# MCU.net
KiCad netlist of a schematic drawn in Altium Designer
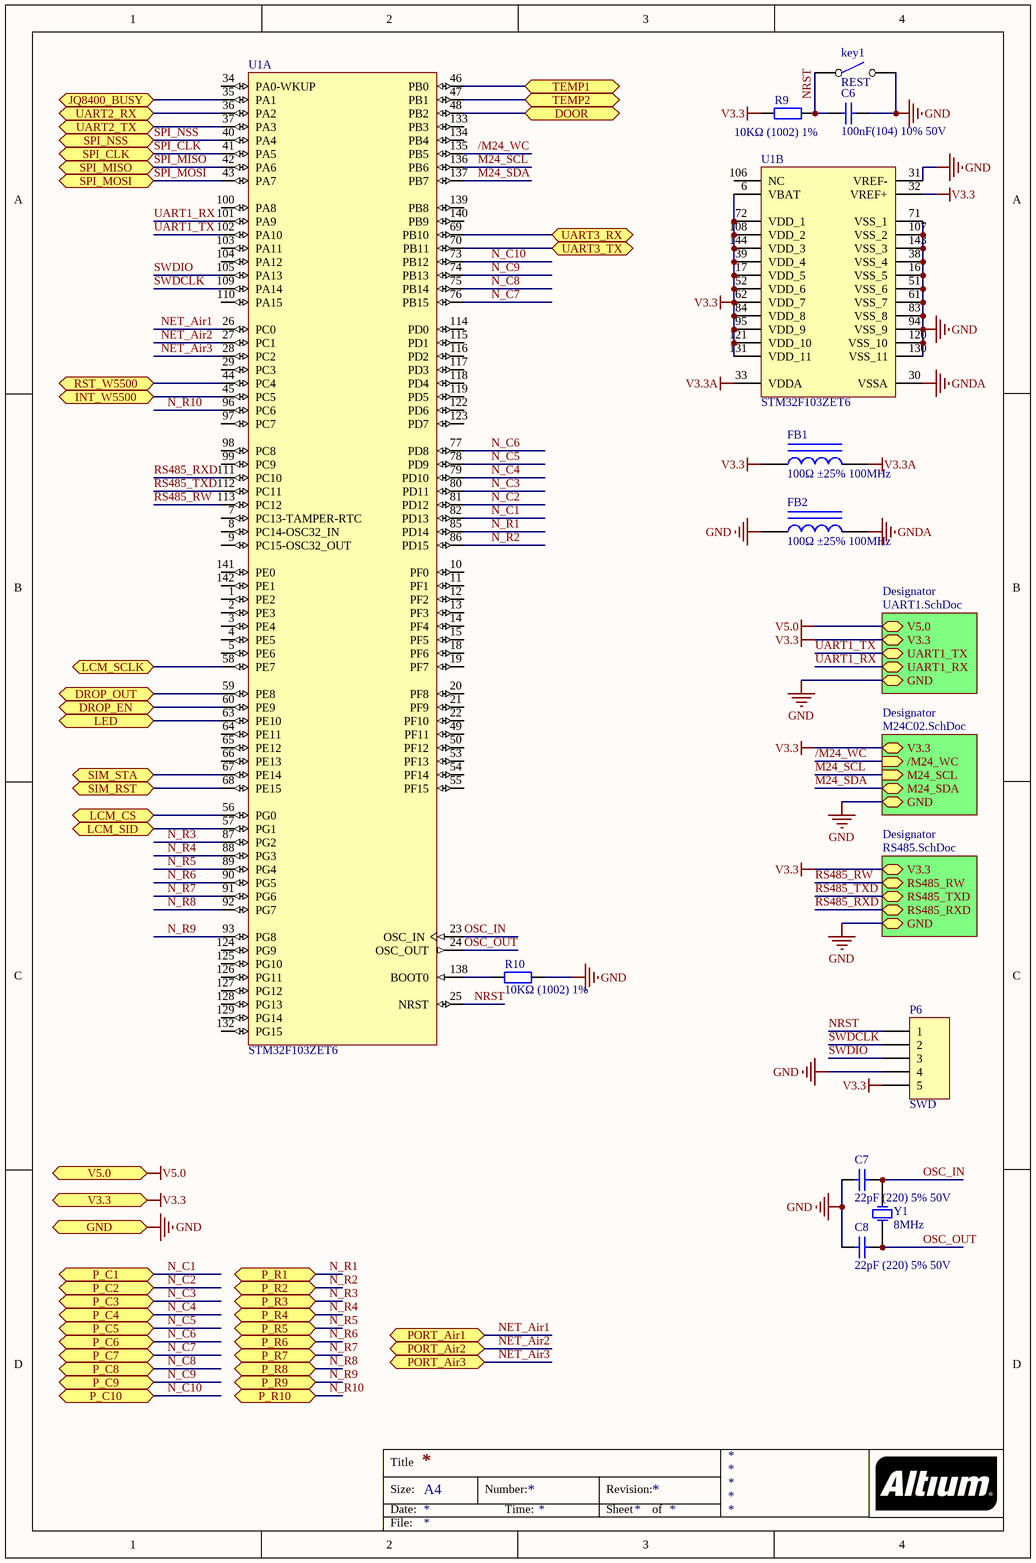
[diagram p0: MCU.SchDoc]

(export (version "E")
  (design (tool "Eeschema 10.0.6"))
  (components
    (comp (ref "C6")
      (value "100nF(104) 10% 50V")
      (footprint "0805_C")
      (description "贴片电容")
      (libsource (lib "Miscellaneous Devices LC") (part "0805 100nF(104) 10% 50V"))
    )
    (comp (ref "C7")
      (value "22pF (220) 5% 50V")
      (footprint "0805_C")
      (description "贴片电容")
      (libsource (lib "Miscellaneous Devices LC") (part "0805 22pF (220) 5% 50V"))
    )
    (comp (ref "C8")
      (value "22pF (220) 5% 50V")
      (footprint "0805_C")
      (description "贴片电容")
      (libsource (lib "Miscellaneous Devices LC") (part "0805 22pF (220) 5% 50V"))
    )
    (comp (ref "FB1")
      (value "100Ω ±25% 100MHz")
      (footprint "0805_L")
      (description "贴片磁珠")
      (libsource (lib "Miscellaneous Devices LC") (part "0805 100Ω 25% 100MHz"))
    )
    (comp (ref "FB2")
      (value "100Ω ±25% 100MHz")
      (footprint "0805_L")
      (description "贴片磁珠")
      (libsource (lib "Miscellaneous Devices LC") (part "0805 100Ω 25% 100MHz"))
    )
    (comp (ref "key1") (value "REST") (footprint "key") (libsource (lib "开关") (part "单刀开关")))
    (comp (ref "P6")
      (value "SWD")
      (footprint "HDR1X5")
      (description "Header, 5-Pin")
      (fields (field (name "PUBLISHER") "Altium Limited"))
      (libsource (lib "Miscellaneous Connectors") (part "Header 5"))
    )
    (comp (ref "R9")
      (value "10KΩ (1002) 1%")
      (footprint "0805_R")
      (description "贴片电阻")
      (libsource (lib "") (part "0805 10KΩ (1002) 1%_1"))
    )
    (comp (ref "R10")
      (value "10KΩ (1002) 1%")
      (footprint "0805_R")
      (description "贴片电阻")
      (libsource (lib "Miscellaneous Devices LC") (part "0805 10KΩ (1002) 1%"))
    )
    (comp (ref "U1")
      (value "STM32F103ZET6")
      (footprint "LQFP-144_20x20x05P")
      (description "ARM")
      (libsource (lib "Miscellaneous Devices LC") (part "STM32F103ZET6"))
    )
    (comp (ref "Y1")
      (value "8MHz")
      (footprint "SMD-5032_2P")
      (description "贴片晶振")
      (libsource (lib "Miscellaneous Devices LC") (part "SMD-5032_2P 8MHz 20ppm 20pF"))
    )
  )
  (nets
    (net (code "1") (name "/DOOR") (class "Default")
      (node (ref "U1") (pin "48") (pinfunction "PB2_48") (pintype "bidirectional"))
    )
    (net (code "2") (name "/DROP_EN") (class "Default")
      (node (ref "U1") (pin "60") (pinfunction "PE9_60") (pintype "bidirectional"))
    )
    (net (code "3") (name "/DROP_OUT") (class "Default")
      (node (ref "U1") (pin "59") (pinfunction "PE8_59") (pintype "bidirectional"))
    )
    (net (code "4") (name "/INT_W5500") (class "Default")
      (node (ref "U1") (pin "45") (pinfunction "PC5_45") (pintype "bidirectional"))
    )
    (net (code "5") (name "/JQ8400_BUSY") (class "Default")
      (node (ref "U1") (pin "35") (pinfunction "PA1_35") (pintype "bidirectional"))
    )
    (net (code "6") (name "/LCM_CS") (class "Default")
      (node (ref "U1") (pin "56") (pinfunction "PG0_56") (pintype "bidirectional"))
    )
    (net (code "7") (name "/LCM_SCLK") (class "Default")
      (node (ref "U1") (pin "58") (pinfunction "PE7_58") (pintype "bidirectional"))
    )
    (net (code "8") (name "/LCM_SID") (class "Default")
      (node (ref "U1") (pin "57") (pinfunction "PG1_57") (pintype "bidirectional"))
    )
    (net (code "9") (name "/LED") (class "Default")
      (node (ref "U1") (pin "63") (pinfunction "PE10_63") (pintype "bidirectional"))
    )
    (net (code "10") (name "/M24_SCL") (class "Default")
      (node (ref "U1") (pin "136") (pinfunction "PB6_136") (pintype "bidirectional"))
    )
    (net (code "11") (name "/M24_SDA") (class "Default")
      (node (ref "U1") (pin "137") (pinfunction "PB7_137") (pintype "bidirectional"))
    )
    (net (code "12") (name "/NET_Air1") (class "Default")
      (node (ref "U1") (pin "26") (pinfunction "PC0_26") (pintype "bidirectional"))
    )
    (net (code "13") (name "/NET_Air2") (class "Default")
      (node (ref "U1") (pin "27") (pinfunction "PC1_27") (pintype "bidirectional"))
    )
    (net (code "14") (name "/NET_Air3") (class "Default")
      (node (ref "U1") (pin "28") (pinfunction "PC2_28") (pintype "bidirectional"))
    )
    (net (code "15") (name "/NRST") (class "Default")
      (node (ref "C6") (pin "1") (pinfunction "1_1") (pintype "passive"))
      (node (ref "P6") (pin "1") (pinfunction "1_1") (pintype "passive"))
      (node (ref "R9") (pin "1") (pinfunction "1_1") (pintype "passive"))
      (node (ref "U1") (pin "25") (pinfunction "NRST_25") (pintype "bidirectional"))
      (node (ref "key1") (pin "1") (pinfunction "1_1") (pintype "passive"))
    )
    (net (code "16") (name "/N_C1") (class "Default")
      (node (ref "U1") (pin "82") (pinfunction "PD13_82") (pintype "bidirectional"))
    )
    (net (code "17") (name "/N_C2") (class "Default")
      (node (ref "U1") (pin "81") (pinfunction "PD12_81") (pintype "bidirectional"))
    )
    (net (code "18") (name "/N_C3") (class "Default")
      (node (ref "U1") (pin "80") (pinfunction "PD11_80") (pintype "bidirectional"))
    )
    (net (code "19") (name "/N_C4") (class "Default")
      (node (ref "U1") (pin "79") (pinfunction "PD10_79") (pintype "bidirectional"))
    )
    (net (code "20") (name "/N_C5") (class "Default")
      (node (ref "U1") (pin "78") (pinfunction "PD9_78") (pintype "bidirectional"))
    )
    (net (code "21") (name "/N_C6") (class "Default")
      (node (ref "U1") (pin "77") (pinfunction "PD8_77") (pintype "bidirectional"))
    )
    (net (code "22") (name "/N_C7") (class "Default")
      (node (ref "U1") (pin "76") (pinfunction "PB15_76") (pintype "bidirectional"))
    )
    (net (code "23") (name "/N_C8") (class "Default")
      (node (ref "U1") (pin "75") (pinfunction "PB14_75") (pintype "bidirectional"))
    )
    (net (code "24") (name "/N_C9") (class "Default")
      (node (ref "U1") (pin "74") (pinfunction "PB13_74") (pintype "bidirectional"))
    )
    (net (code "25") (name "/N_C10") (class "Default")
      (node (ref "U1") (pin "73") (pinfunction "PB12_73") (pintype "bidirectional"))
    )
    (net (code "26") (name "/N_R1") (class "Default")
      (node (ref "U1") (pin "85") (pinfunction "PD14_85") (pintype "bidirectional"))
    )
    (net (code "27") (name "/N_R2") (class "Default")
      (node (ref "U1") (pin "86") (pinfunction "PD15_86") (pintype "bidirectional"))
    )
    (net (code "28") (name "/N_R3") (class "Default")
      (node (ref "U1") (pin "87") (pinfunction "PG2_87") (pintype "bidirectional"))
    )
    (net (code "29") (name "/N_R4") (class "Default")
      (node (ref "U1") (pin "88") (pinfunction "PG3_88") (pintype "bidirectional"))
    )
    (net (code "30") (name "/N_R5") (class "Default")
      (node (ref "U1") (pin "89") (pinfunction "PG4_89") (pintype "bidirectional"))
    )
    (net (code "31") (name "/N_R6") (class "Default")
      (node (ref "U1") (pin "90") (pinfunction "PG5_90") (pintype "bidirectional"))
    )
    (net (code "32") (name "/N_R7") (class "Default")
      (node (ref "U1") (pin "91") (pinfunction "PG6_91") (pintype "bidirectional"))
    )
    (net (code "33") (name "/N_R8") (class "Default")
      (node (ref "U1") (pin "92") (pinfunction "PG7_92") (pintype "bidirectional"))
    )
    (net (code "34") (name "/N_R9") (class "Default")
      (node (ref "U1") (pin "93") (pinfunction "PG8_93") (pintype "bidirectional"))
    )
    (net (code "35") (name "/N_R10") (class "Default")
      (node (ref "U1") (pin "96") (pinfunction "PC6_96") (pintype "bidirectional"))
    )
    (net (code "36") (name "/OSC_IN") (class "Default")
      (node (ref "C7") (pin "1") (pinfunction "1_1") (pintype "passive"))
      (node (ref "U1") (pin "23") (pinfunction "OSC_IN_23") (pintype "input"))
      (node (ref "Y1") (pin "1") (pinfunction "OSC1_1") (pintype "passive"))
    )
    (net (code "37") (name "/OSC_OUT") (class "Default")
      (node (ref "C8") (pin "1") (pinfunction "1_1") (pintype "passive"))
      (node (ref "U1") (pin "24") (pinfunction "OSC_OUT_24") (pintype "output"))
      (node (ref "Y1") (pin "2") (pinfunction "OSC2_2") (pintype "passive"))
    )
    (net (code "38") (name "/RS485_RW") (class "Default")
      (node (ref "U1") (pin "113") (pinfunction "PC12_113") (pintype "bidirectional"))
    )
    (net (code "39") (name "/RS485_RXD") (class "Default")
      (node (ref "U1") (pin "111") (pinfunction "PC10_111") (pintype "bidirectional"))
    )
    (net (code "40") (name "/RS485_TXD") (class "Default")
      (node (ref "U1") (pin "112") (pinfunction "PC11_112") (pintype "bidirectional"))
    )
    (net (code "41") (name "/RST_W5500") (class "Default")
      (node (ref "U1") (pin "44") (pinfunction "PC4_44") (pintype "bidirectional"))
    )
    (net (code "42") (name "/SIM_RST") (class "Default")
      (node (ref "U1") (pin "68") (pinfunction "PE15_68") (pintype "bidirectional"))
    )
    (net (code "43") (name "/SIM_STA") (class "Default")
      (node (ref "U1") (pin "67") (pinfunction "PE14_67") (pintype "bidirectional"))
    )
    (net (code "44") (name "/SPI_CLK") (class "Default")
      (node (ref "U1") (pin "41") (pinfunction "PA5_41") (pintype "bidirectional"))
    )
    (net (code "45") (name "/SPI_MISO") (class "Default")
      (node (ref "U1") (pin "42") (pinfunction "PA6_42") (pintype "bidirectional"))
    )
    (net (code "46") (name "/SPI_MOSI") (class "Default")
      (node (ref "U1") (pin "43") (pinfunction "PA7_43") (pintype "bidirectional"))
    )
    (net (code "47") (name "/SPI_NSS") (class "Default")
      (node (ref "U1") (pin "40") (pinfunction "PA4_40") (pintype "bidirectional"))
    )
    (net (code "48") (name "/SWDCLK") (class "Default")
      (node (ref "P6") (pin "2") (pinfunction "2_2") (pintype "passive"))
      (node (ref "U1") (pin "109") (pinfunction "PA14_109") (pintype "bidirectional"))
    )
    (net (code "49") (name "/SWDIO") (class "Default")
      (node (ref "P6") (pin "3") (pinfunction "3_3") (pintype "passive"))
      (node (ref "U1") (pin "105") (pinfunction "PA13_105") (pintype "bidirectional"))
    )
    (net (code "50") (name "/TEMP1") (class "Default")
      (node (ref "U1") (pin "46") (pinfunction "PB0_46") (pintype "bidirectional"))
    )
    (net (code "51") (name "/TEMP2") (class "Default")
      (node (ref "U1") (pin "47") (pinfunction "PB1_47") (pintype "bidirectional"))
    )
    (net (code "52") (name "/UART1_RX") (class "Default")
      (node (ref "U1") (pin "101") (pinfunction "PA9_101") (pintype "bidirectional"))
    )
    (net (code "53") (name "/UART1_TX") (class "Default")
      (node (ref "U1") (pin "102") (pinfunction "PA10_102") (pintype "bidirectional"))
    )
    (net (code "54") (name "/UART2_RX") (class "Default")
      (node (ref "U1") (pin "36") (pinfunction "PA2_36") (pintype "bidirectional"))
    )
    (net (code "55") (name "/UART2_TX") (class "Default")
      (node (ref "U1") (pin "37") (pinfunction "PA3_37") (pintype "bidirectional"))
    )
    (net (code "56") (name "/UART3_RX") (class "Default")
      (node (ref "U1") (pin "69") (pinfunction "PB10_69") (pintype "bidirectional"))
    )
    (net (code "57") (name "/UART3_TX") (class "Default")
      (node (ref "U1") (pin "70") (pinfunction "PB11_70") (pintype "bidirectional"))
    )
    (net (code "58") (name "/{slash}M24_WC") (class "Default")
      (node (ref "U1") (pin "135") (pinfunction "PB5_135") (pintype "bidirectional"))
    )
    (net (code "59") (name "GND") (class "Default")
      (node (ref "C6") (pin "2") (pinfunction "2_2") (pintype "passive"))
      (node (ref "C7") (pin "2") (pinfunction "2_2") (pintype "passive"))
      (node (ref "C8") (pin "2") (pinfunction "2_2") (pintype "passive"))
      (node (ref "FB2") (pin "1") (pinfunction "1_1") (pintype "passive"))
      (node (ref "P6") (pin "4") (pinfunction "4_4") (pintype "passive"))
      (node (ref "R10") (pin "2") (pinfunction "2_2") (pintype "passive"))
      (node (ref "U1") (pin "107") (pinfunction "VSS_2_107") (pintype "power_in"))
      (node (ref "U1") (pin "120") (pinfunction "VSS_10_120") (pintype "power_in"))
      (node (ref "U1") (pin "130") (pinfunction "VSS_11_130") (pintype "power_in"))
      (node (ref "U1") (pin "143") (pinfunction "VSS_3_143") (pintype "power_in"))
      (node (ref "U1") (pin "16") (pinfunction "VSS_5_16") (pintype "power_in"))
      (node (ref "U1") (pin "31") (pinfunction "VREF-_31") (pintype "power_in"))
      (node (ref "U1") (pin "38") (pinfunction "VSS_4_38") (pintype "power_in"))
      (node (ref "U1") (pin "51") (pinfunction "VSS_6_51") (pintype "power_in"))
      (node (ref "U1") (pin "61") (pinfunction "VSS_7_61") (pintype "power_in"))
      (node (ref "U1") (pin "71") (pinfunction "VSS_1_71") (pintype "power_in"))
      (node (ref "U1") (pin "83") (pinfunction "VSS_8_83") (pintype "power_in"))
      (node (ref "U1") (pin "94") (pinfunction "VSS_9_94") (pintype "power_in"))
      (node (ref "key1") (pin "2") (pinfunction "2_2") (pintype "passive"))
    )
    (net (code "60") (name "GNDA") (class "Default")
      (node (ref "FB2") (pin "2") (pinfunction "2_2") (pintype "passive"))
      (node (ref "U1") (pin "30") (pinfunction "VSSA_30") (pintype "power_in"))
    )
    (net (code "61") (name "Net-(U1A-BOOT0)") (class "Default")
      (node (ref "R10") (pin "1") (pinfunction "1_1") (pintype "passive"))
      (node (ref "U1") (pin "138") (pinfunction "BOOT0_138") (pintype "input"))
    )
    (net (code "62") (name "V3.3") (class "Default")
      (node (ref "FB1") (pin "1") (pinfunction "1_1") (pintype "passive"))
      (node (ref "P6") (pin "5") (pinfunction "5_5") (pintype "passive"))
      (node (ref "R9") (pin "2") (pinfunction "2_2") (pintype "passive"))
      (node (ref "U1") (pin "108") (pinfunction "VDD_2_108") (pintype "power_in"))
      (node (ref "U1") (pin "121") (pinfunction "VDD_10_121") (pintype "power_in"))
      (node (ref "U1") (pin "131") (pinfunction "VDD_11_131") (pintype "power_in"))
      (node (ref "U1") (pin "144") (pinfunction "VDD_3_144") (pintype "power_in"))
      (node (ref "U1") (pin "17") (pinfunction "VDD_5_17") (pintype "power_in"))
      (node (ref "U1") (pin "32") (pinfunction "VREF+_32") (pintype "power_in"))
      (node (ref "U1") (pin "39") (pinfunction "VDD_4_39") (pintype "power_in"))
      (node (ref "U1") (pin "52") (pinfunction "VDD_6_52") (pintype "power_in"))
      (node (ref "U1") (pin "6") (pinfunction "VBAT_6") (pintype "power_in"))
      (node (ref "U1") (pin "62") (pinfunction "VDD_7_62") (pintype "power_in"))
      (node (ref "U1") (pin "72") (pinfunction "VDD_1_72") (pintype "power_in"))
      (node (ref "U1") (pin "84") (pinfunction "VDD_8_84") (pintype "power_in"))
      (node (ref "U1") (pin "95") (pinfunction "VDD_9_95") (pintype "power_in"))
    )
    (net (code "63") (name "V3.3A") (class "Default")
      (node (ref "FB1") (pin "2") (pinfunction "2_2") (pintype "passive"))
      (node (ref "U1") (pin "33") (pinfunction "VDDA_33") (pintype "power_in"))
    )
    (net (code "65") (name "unconnected-(U1A-PA0-WKUP-Pad34)") (class "Default")
      (node (ref "U1") (pin "34") (pinfunction "PA0-WKUP_34") (pintype "bidirectional"))
    )
    (net (code "66") (name "unconnected-(U1A-PA8-Pad100)") (class "Default")
      (node (ref "U1") (pin "100") (pinfunction "PA8_100") (pintype "bidirectional"))
    )
    (net (code "67") (name "unconnected-(U1A-PA11-Pad103)") (class "Default")
      (node (ref "U1") (pin "103") (pinfunction "PA11_103") (pintype "bidirectional"))
    )
    (net (code "68") (name "unconnected-(U1A-PA12-Pad104)") (class "Default")
      (node (ref "U1") (pin "104") (pinfunction "PA12_104") (pintype "bidirectional"))
    )
    (net (code "69") (name "unconnected-(U1A-PA15-Pad110)") (class "Default")
      (node (ref "U1") (pin "110") (pinfunction "PA15_110") (pintype "bidirectional"))
    )
    (net (code "70") (name "unconnected-(U1A-PB3-Pad133)") (class "Default")
      (node (ref "U1") (pin "133") (pinfunction "PB3_133") (pintype "bidirectional"))
    )
    (net (code "71") (name "unconnected-(U1A-PB4-Pad134)") (class "Default")
      (node (ref "U1") (pin "134") (pinfunction "PB4_134") (pintype "bidirectional"))
    )
    (net (code "72") (name "unconnected-(U1A-PB8-Pad139)") (class "Default")
      (node (ref "U1") (pin "139") (pinfunction "PB8_139") (pintype "bidirectional"))
    )
    (net (code "73") (name "unconnected-(U1A-PB9-Pad140)") (class "Default")
      (node (ref "U1") (pin "140") (pinfunction "PB9_140") (pintype "bidirectional"))
    )
    (net (code "74") (name "unconnected-(U1A-PC3-Pad29)") (class "Default")
      (node (ref "U1") (pin "29") (pinfunction "PC3_29") (pintype "bidirectional"))
    )
    (net (code "75") (name "unconnected-(U1A-PC7-Pad97)") (class "Default")
      (node (ref "U1") (pin "97") (pinfunction "PC7_97") (pintype "bidirectional"))
    )
    (net (code "76") (name "unconnected-(U1A-PC8-Pad98)") (class "Default")
      (node (ref "U1") (pin "98") (pinfunction "PC8_98") (pintype "bidirectional"))
    )
    (net (code "77") (name "unconnected-(U1A-PC9-Pad99)") (class "Default")
      (node (ref "U1") (pin "99") (pinfunction "PC9_99") (pintype "bidirectional"))
    )
    (net (code "78") (name "unconnected-(U1A-PC13-TAMPER-RTC-Pad7)") (class "Default")
      (node (ref "U1") (pin "7") (pinfunction "PC13-TAMPER-RTC_7") (pintype "bidirectional"))
    )
    (net (code "79") (name "unconnected-(U1A-PC14-OSC32_IN-Pad8)") (class "Default")
      (node (ref "U1") (pin "8") (pinfunction "PC14-OSC32_IN_8") (pintype "bidirectional"))
    )
    (net (code "80") (name "unconnected-(U1A-PC15-OSC32_OUT-Pad9)") (class "Default")
      (node (ref "U1") (pin "9") (pinfunction "PC15-OSC32_OUT_9") (pintype "bidirectional"))
    )
    (net (code "81") (name "unconnected-(U1A-PD0-Pad114)") (class "Default")
      (node (ref "U1") (pin "114") (pinfunction "PD0_114") (pintype "bidirectional"))
    )
    (net (code "82") (name "unconnected-(U1A-PD1-Pad115)") (class "Default")
      (node (ref "U1") (pin "115") (pinfunction "PD1_115") (pintype "bidirectional"))
    )
    (net (code "83") (name "unconnected-(U1A-PD2-Pad116)") (class "Default")
      (node (ref "U1") (pin "116") (pinfunction "PD2_116") (pintype "bidirectional"))
    )
    (net (code "84") (name "unconnected-(U1A-PD3-Pad117)") (class "Default")
      (node (ref "U1") (pin "117") (pinfunction "PD3_117") (pintype "bidirectional"))
    )
    (net (code "85") (name "unconnected-(U1A-PD4-Pad118)") (class "Default")
      (node (ref "U1") (pin "118") (pinfunction "PD4_118") (pintype "bidirectional"))
    )
    (net (code "86") (name "unconnected-(U1A-PD5-Pad119)") (class "Default")
      (node (ref "U1") (pin "119") (pinfunction "PD5_119") (pintype "bidirectional"))
    )
    (net (code "87") (name "unconnected-(U1A-PD6-Pad122)") (class "Default")
      (node (ref "U1") (pin "122") (pinfunction "PD6_122") (pintype "bidirectional"))
    )
    (net (code "88") (name "unconnected-(U1A-PD7-Pad123)") (class "Default")
      (node (ref "U1") (pin "123") (pinfunction "PD7_123") (pintype "bidirectional"))
    )
    (net (code "89") (name "unconnected-(U1A-PE0-Pad141)") (class "Default")
      (node (ref "U1") (pin "141") (pinfunction "PE0_141") (pintype "bidirectional"))
    )
    (net (code "90") (name "unconnected-(U1A-PE1-Pad142)") (class "Default")
      (node (ref "U1") (pin "142") (pinfunction "PE1_142") (pintype "bidirectional"))
    )
    (net (code "91") (name "unconnected-(U1A-PE2-Pad1)") (class "Default")
      (node (ref "U1") (pin "1") (pinfunction "PE2_1") (pintype "bidirectional"))
    )
    (net (code "92") (name "unconnected-(U1A-PE3-Pad2)") (class "Default")
      (node (ref "U1") (pin "2") (pinfunction "PE3_2") (pintype "bidirectional"))
    )
    (net (code "93") (name "unconnected-(U1A-PE4-Pad3)") (class "Default")
      (node (ref "U1") (pin "3") (pinfunction "PE4_3") (pintype "bidirectional"))
    )
    (net (code "94") (name "unconnected-(U1A-PE5-Pad4)") (class "Default")
      (node (ref "U1") (pin "4") (pinfunction "PE5_4") (pintype "bidirectional"))
    )
    (net (code "95") (name "unconnected-(U1A-PE6-Pad5)") (class "Default")
      (node (ref "U1") (pin "5") (pinfunction "PE6_5") (pintype "bidirectional"))
    )
    (net (code "96") (name "unconnected-(U1A-PE11-Pad64)") (class "Default")
      (node (ref "U1") (pin "64") (pinfunction "PE11_64") (pintype "bidirectional"))
    )
    (net (code "97") (name "unconnected-(U1A-PE12-Pad65)") (class "Default")
      (node (ref "U1") (pin "65") (pinfunction "PE12_65") (pintype "bidirectional"))
    )
    (net (code "98") (name "unconnected-(U1A-PE13-Pad66)") (class "Default")
      (node (ref "U1") (pin "66") (pinfunction "PE13_66") (pintype "bidirectional"))
    )
    (net (code "99") (name "unconnected-(U1A-PF0-Pad10)") (class "Default")
      (node (ref "U1") (pin "10") (pinfunction "PF0_10") (pintype "bidirectional"))
    )
    (net (code "100") (name "unconnected-(U1A-PF1-Pad11)") (class "Default")
      (node (ref "U1") (pin "11") (pinfunction "PF1_11") (pintype "bidirectional"))
    )
    (net (code "101") (name "unconnected-(U1A-PF2-Pad12)") (class "Default")
      (node (ref "U1") (pin "12") (pinfunction "PF2_12") (pintype "bidirectional"))
    )
    (net (code "102") (name "unconnected-(U1A-PF3-Pad13)") (class "Default")
      (node (ref "U1") (pin "13") (pinfunction "PF3_13") (pintype "bidirectional"))
    )
    (net (code "103") (name "unconnected-(U1A-PF4-Pad14)") (class "Default")
      (node (ref "U1") (pin "14") (pinfunction "PF4_14") (pintype "bidirectional"))
    )
    (net (code "104") (name "unconnected-(U1A-PF5-Pad15)") (class "Default")
      (node (ref "U1") (pin "15") (pinfunction "PF5_15") (pintype "bidirectional"))
    )
    (net (code "105") (name "unconnected-(U1A-PF6-Pad18)") (class "Default")
      (node (ref "U1") (pin "18") (pinfunction "PF6_18") (pintype "bidirectional"))
    )
    (net (code "106") (name "unconnected-(U1A-PF7-Pad19)") (class "Default")
      (node (ref "U1") (pin "19") (pinfunction "PF7_19") (pintype "bidirectional"))
    )
    (net (code "107") (name "unconnected-(U1A-PF8-Pad20)") (class "Default")
      (node (ref "U1") (pin "20") (pinfunction "PF8_20") (pintype "bidirectional"))
    )
    (net (code "108") (name "unconnected-(U1A-PF9-Pad21)") (class "Default")
      (node (ref "U1") (pin "21") (pinfunction "PF9_21") (pintype "bidirectional"))
    )
    (net (code "109") (name "unconnected-(U1A-PF10-Pad22)") (class "Default")
      (node (ref "U1") (pin "22") (pinfunction "PF10_22") (pintype "bidirectional"))
    )
    (net (code "110") (name "unconnected-(U1A-PF11-Pad49)") (class "Default")
      (node (ref "U1") (pin "49") (pinfunction "PF11_49") (pintype "bidirectional"))
    )
    (net (code "111") (name "unconnected-(U1A-PF12-Pad50)") (class "Default")
      (node (ref "U1") (pin "50") (pinfunction "PF12_50") (pintype "bidirectional"))
    )
    (net (code "112") (name "unconnected-(U1A-PF13-Pad53)") (class "Default")
      (node (ref "U1") (pin "53") (pinfunction "PF13_53") (pintype "bidirectional"))
    )
    (net (code "113") (name "unconnected-(U1A-PF14-Pad54)") (class "Default")
      (node (ref "U1") (pin "54") (pinfunction "PF14_54") (pintype "bidirectional"))
    )
    (net (code "114") (name "unconnected-(U1A-PF15-Pad55)") (class "Default")
      (node (ref "U1") (pin "55") (pinfunction "PF15_55") (pintype "bidirectional"))
    )
    (net (code "115") (name "unconnected-(U1A-PG9-Pad124)") (class "Default")
      (node (ref "U1") (pin "124") (pinfunction "PG9_124") (pintype "bidirectional"))
    )
    (net (code "116") (name "unconnected-(U1A-PG10-Pad125)") (class "Default")
      (node (ref "U1") (pin "125") (pinfunction "PG10_125") (pintype "bidirectional"))
    )
    (net (code "117") (name "unconnected-(U1A-PG11-Pad126)") (class "Default")
      (node (ref "U1") (pin "126") (pinfunction "PG11_126") (pintype "bidirectional"))
    )
    (net (code "118") (name "unconnected-(U1A-PG12-Pad127)") (class "Default")
      (node (ref "U1") (pin "127") (pinfunction "PG12_127") (pintype "bidirectional"))
    )
    (net (code "119") (name "unconnected-(U1A-PG13-Pad128)") (class "Default")
      (node (ref "U1") (pin "128") (pinfunction "PG13_128") (pintype "bidirectional"))
    )
    (net (code "120") (name "unconnected-(U1A-PG14-Pad129)") (class "Default")
      (node (ref "U1") (pin "129") (pinfunction "PG14_129") (pintype "bidirectional"))
    )
    (net (code "121") (name "unconnected-(U1A-PG15-Pad132)") (class "Default")
      (node (ref "U1") (pin "132") (pinfunction "PG15_132") (pintype "bidirectional"))
    )
    (net (code "122") (name "unconnected-(U1B-NC-Pad106)") (class "Default")
      (node (ref "U1") (pin "106") (pinfunction "NC_106") (pintype "passive"))
    )
  )
)
